# hcsr04bracket.net
KiCad netlist of a schematic drawn in EAGLE
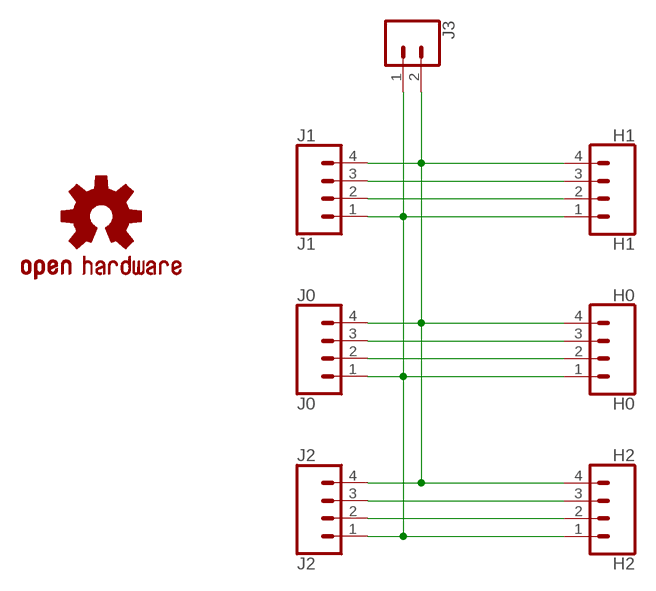
[diagram p0: schematic, sheet 1]

(export (version "E")
  (design (tool "Eeschema 10.0.6"))
  (components
    (comp (ref "H0")
      (value "H0")
      (footprint "eagle-import:1X04")
      (libsource (lib "eagle-import") (part "CONN_04"))
    )
    (comp (ref "H1")
      (value "H1")
      (footprint "eagle-import:1X04")
      (libsource (lib "eagle-import") (part "CONN_04"))
    )
    (comp (ref "H2")
      (value "H2")
      (footprint "eagle-import:1X04")
      (libsource (lib "eagle-import") (part "CONN_04"))
    )
    (comp (ref "J0")
      (value "J0")
      (footprint "eagle-import:1X04")
      (libsource (lib "eagle-import") (part "CONN_04"))
    )
    (comp (ref "J1")
      (value "J1")
      (footprint "eagle-import:1X04")
      (libsource (lib "eagle-import") (part "CONN_04"))
    )
    (comp (ref "J2")
      (value "J2")
      (footprint "eagle-import:1X04")
      (libsource (lib "eagle-import") (part "CONN_04"))
    )
    (comp (ref "J3")
      (value "CONN_02")
      (footprint "eagle-import:1X02")
      (libsource (lib "eagle-import") (part "CONN_02"))
    )
    (comp (ref "LOGO1")
      (value "OSHW-LOGOS")
      (footprint "eagle-import:OSHW-LOGO-S")
      (libsource (lib "eagle-import") (part "OSHW-LOGOS"))
    )
  )
  (nets
    (net (code "1") (name "Net-(H0-Pad1)") (class "Default")
      (node (ref "H0") (pin "1") (pinfunction "1_1") (pintype "passive"))
      (node (ref "H1") (pin "1") (pinfunction "1_1") (pintype "passive"))
      (node (ref "H2") (pin "1") (pinfunction "1_1") (pintype "passive"))
      (node (ref "J0") (pin "1") (pinfunction "1_1") (pintype "passive"))
      (node (ref "J1") (pin "1") (pinfunction "1_1") (pintype "passive"))
      (node (ref "J2") (pin "1") (pinfunction "1_1") (pintype "passive"))
      (node (ref "J3") (pin "1") (pinfunction "1_1") (pintype "passive"))
    )
    (net (code "2") (name "Net-(H0-Pad2)") (class "Default")
      (node (ref "H0") (pin "2") (pinfunction "2_2") (pintype "passive"))
      (node (ref "J0") (pin "2") (pinfunction "2_2") (pintype "passive"))
    )
    (net (code "3") (name "Net-(H0-Pad3)") (class "Default")
      (node (ref "H0") (pin "3") (pinfunction "3_3") (pintype "passive"))
      (node (ref "J0") (pin "3") (pinfunction "3_3") (pintype "passive"))
    )
    (net (code "4") (name "Net-(H0-Pad4)") (class "Default")
      (node (ref "H0") (pin "4") (pinfunction "4_4") (pintype "passive"))
      (node (ref "H1") (pin "4") (pinfunction "4_4") (pintype "passive"))
      (node (ref "H2") (pin "4") (pinfunction "4_4") (pintype "passive"))
      (node (ref "J0") (pin "4") (pinfunction "4_4") (pintype "passive"))
      (node (ref "J1") (pin "4") (pinfunction "4_4") (pintype "passive"))
      (node (ref "J2") (pin "4") (pinfunction "4_4") (pintype "passive"))
      (node (ref "J3") (pin "2") (pinfunction "2_2") (pintype "passive"))
    )
    (net (code "5") (name "Net-(H1-Pad2)") (class "Default")
      (node (ref "H1") (pin "2") (pinfunction "2_2") (pintype "passive"))
      (node (ref "J1") (pin "2") (pinfunction "2_2") (pintype "passive"))
    )
    (net (code "6") (name "Net-(H1-Pad3)") (class "Default")
      (node (ref "H1") (pin "3") (pinfunction "3_3") (pintype "passive"))
      (node (ref "J1") (pin "3") (pinfunction "3_3") (pintype "passive"))
    )
    (net (code "7") (name "Net-(H2-Pad2)") (class "Default")
      (node (ref "H2") (pin "2") (pinfunction "2_2") (pintype "passive"))
      (node (ref "J2") (pin "2") (pinfunction "2_2") (pintype "passive"))
    )
    (net (code "8") (name "Net-(H2-Pad3)") (class "Default")
      (node (ref "H2") (pin "3") (pinfunction "3_3") (pintype "passive"))
      (node (ref "J2") (pin "3") (pinfunction "3_3") (pintype "passive"))
    )
  )
)
